# USB_hub.net
KiCad netlist of a schematic drawn in EasyEDA Pro
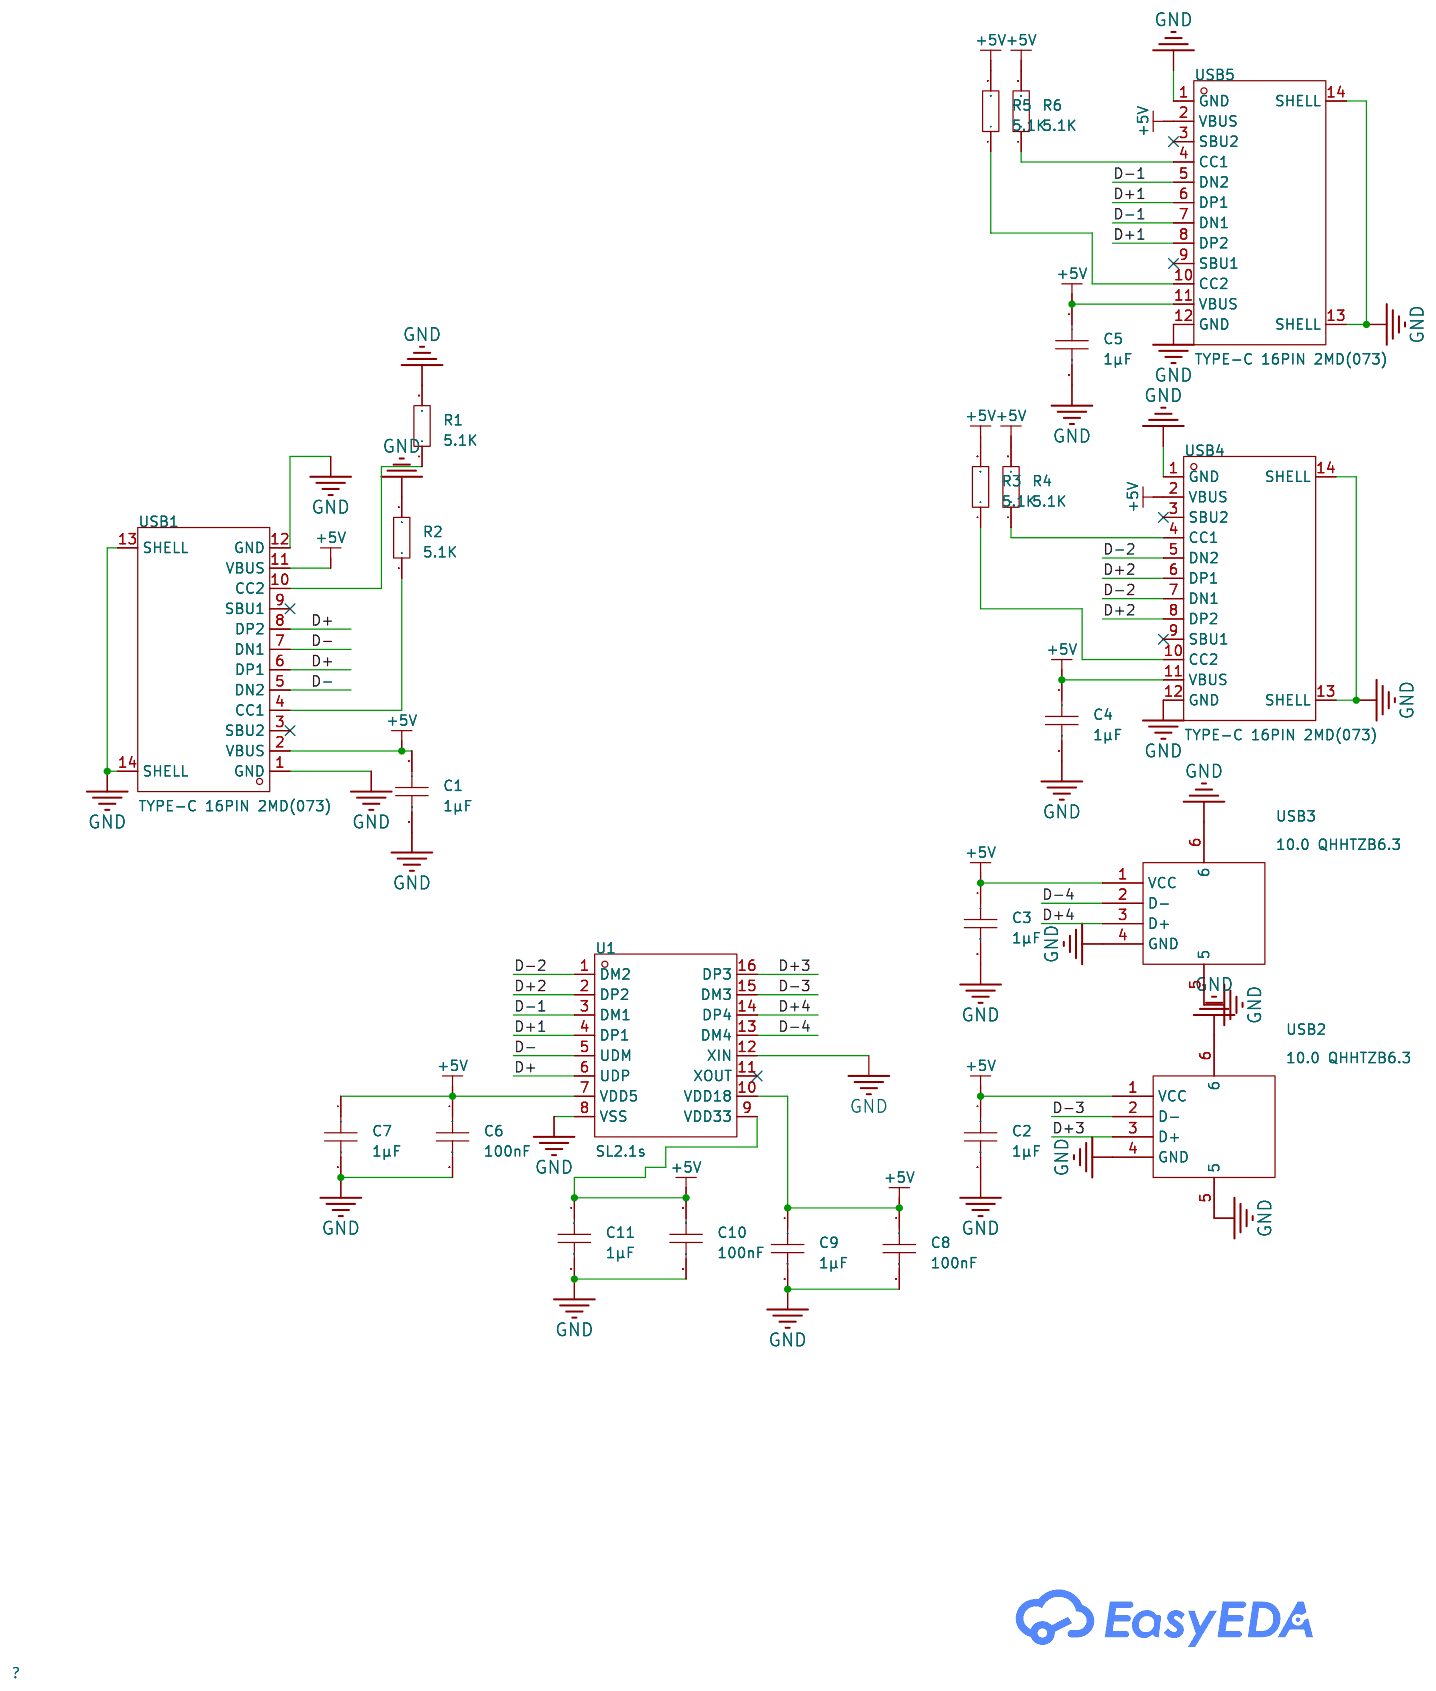
[diagram p0: schematic sheet]

(export (version "E")
  (design (tool "Eeschema 10.0.6"))
  (components
    (comp (ref "C1") (value "1µF") (footprint "easyedapro:C0603") (libsource (lib "easyedapro") (part "CAP")))
    (comp (ref "C2") (value "1µF") (footprint "easyedapro:C0603") (libsource (lib "easyedapro") (part "CAP")))
    (comp (ref "C3") (value "1µF") (footprint "easyedapro:C0603") (libsource (lib "easyedapro") (part "CAP")))
    (comp (ref "C4") (value "1µF") (footprint "easyedapro:C0603") (libsource (lib "easyedapro") (part "CAP")))
    (comp (ref "C5") (value "1µF") (footprint "easyedapro:C0603") (libsource (lib "easyedapro") (part "CAP")))
    (comp (ref "C6")
      (value "100nF")
      (footprint "easyedapro:C0603")
      (libsource (lib "easyedapro") (part "CAP"))
    )
    (comp (ref "C7") (value "1µF") (footprint "easyedapro:C0603") (libsource (lib "easyedapro") (part "CAP")))
    (comp (ref "C8")
      (value "100nF")
      (footprint "easyedapro:C0603")
      (libsource (lib "easyedapro") (part "CAP"))
    )
    (comp (ref "C9") (value "1µF") (footprint "easyedapro:C0603") (libsource (lib "easyedapro") (part "CAP")))
    (comp (ref "C10")
      (value "100nF")
      (footprint "easyedapro:C0603")
      (libsource (lib "easyedapro") (part "CAP"))
    )
    (comp (ref "C11")
      (value "1µF")
      (footprint "easyedapro:C0603")
      (libsource (lib "easyedapro") (part "CAP"))
    )
    (comp (ref "R1")
      (value "5.1K")
      (footprint "easyedapro:R0603")
      (libsource (lib "easyedapro") (part "Res"))
    )
    (comp (ref "R2")
      (value "5.1K")
      (footprint "easyedapro:R0603")
      (libsource (lib "easyedapro") (part "Res"))
    )
    (comp (ref "R3")
      (value "5.1K")
      (footprint "easyedapro:R0603")
      (libsource (lib "easyedapro") (part "Res"))
    )
    (comp (ref "R4")
      (value "5.1K")
      (footprint "easyedapro:R0603")
      (libsource (lib "easyedapro") (part "Res"))
    )
    (comp (ref "R5")
      (value "5.1K")
      (footprint "easyedapro:R0603")
      (libsource (lib "easyedapro") (part "Res"))
    )
    (comp (ref "R6")
      (value "5.1K")
      (footprint "easyedapro:R0603")
      (libsource (lib "easyedapro") (part "Res"))
    )
    (comp (ref "U1")
      (value "SL2.1s")
      (footprint "easyedapro:SSOP-16_L4.6-W2.6-P0.53-LS4.0-BL")
      (fields (field (name "Manufacturer") "CoreChips(和芯润德)"))
      (libsource (lib "easyedapro") (part "SL2.1S"))
    )
    (comp (ref "USB1")
      (value "TYPE-C 16PIN 2MD(073)")
      (footprint "easyedapro:USB-C-SMD_TYPE-C-6PIN-2MD-073")
      (fields (field (name "Manufacturer") "SHOU HAN(首韩)"))
      (libsource (lib "easyedapro") (part "TYPE-C 16PIN 2MD(073)"))
    )
    (comp (ref "USB2")
      (value "10.0 QHHTZB6.3")
      (footprint "easyedapro:USB-A-TH_10.0QHHTZB6.3")
      (fields (field (name "Manufacturer") "SHOU HAN(首韩)"))
      (libsource (lib "easyedapro") (part "10.0 QHHTZB6.3"))
    )
    (comp (ref "USB3")
      (value "10.0 QHHTZB6.3")
      (footprint "easyedapro:USB-A-TH_10.0QHHTZB6.3")
      (fields (field (name "Manufacturer") "SHOU HAN(首韩)"))
      (libsource (lib "easyedapro") (part "10.0 QHHTZB6.3"))
    )
    (comp (ref "USB4")
      (value "TYPE-C 16PIN 2MD(073)")
      (footprint "easyedapro:USB-C-SMD_TYPE-C-6PIN-2MD-073")
      (fields (field (name "Manufacturer") "SHOU HAN(首韩)"))
      (libsource (lib "easyedapro") (part "TYPE-C 16PIN 2MD(073)"))
    )
    (comp (ref "USB5")
      (value "TYPE-C 16PIN 2MD(073)")
      (footprint "easyedapro:USB-C-SMD_TYPE-C-6PIN-2MD-073")
      (fields (field (name "Manufacturer") "SHOU HAN(首韩)"))
      (libsource (lib "easyedapro") (part "TYPE-C 16PIN 2MD(073)"))
    )
  )
  (nets
    (net (code "1") (name "+5V") (class "Default")
      (node (ref "C1") (pin "1") (pinfunction "1_1") (pintype "input"))
      (node (ref "C10") (pin "1") (pinfunction "1_1") (pintype "input"))
      (node (ref "C11") (pin "1") (pinfunction "1_1") (pintype "input"))
      (node (ref "C2") (pin "1") (pinfunction "1_1") (pintype "input"))
      (node (ref "C3") (pin "1") (pinfunction "1_1") (pintype "input"))
      (node (ref "C4") (pin "1") (pinfunction "1_1") (pintype "input"))
      (node (ref "C5") (pin "1") (pinfunction "1_1") (pintype "input"))
      (node (ref "C6") (pin "1") (pinfunction "1_1") (pintype "input"))
      (node (ref "C7") (pin "1") (pinfunction "1_1") (pintype "input"))
      (node (ref "C8") (pin "1") (pinfunction "1_1") (pintype "input"))
      (node (ref "C9") (pin "1") (pinfunction "1_1") (pintype "input"))
      (node (ref "R3") (pin "2") (pinfunction "2_2") (pintype "input"))
      (node (ref "R4") (pin "2") (pinfunction "2_2") (pintype "input"))
      (node (ref "R5") (pin "2") (pinfunction "2_2") (pintype "input"))
      (node (ref "R6") (pin "2") (pinfunction "2_2") (pintype "input"))
      (node (ref "U1") (pin "10") (pinfunction "VDD18_10") (pintype "unspecified"))
      (node (ref "U1") (pin "7") (pinfunction "VDD5_7") (pintype "unspecified"))
      (node (ref "U1") (pin "9") (pinfunction "VDD33_9") (pintype "unspecified"))
      (node (ref "USB1") (pin "11") (pinfunction "VBUS_11") (pintype "unspecified"))
      (node (ref "USB1") (pin "2") (pinfunction "VBUS_2") (pintype "unspecified"))
      (node (ref "USB2") (pin "1") (pinfunction "VCC_1") (pintype "unspecified"))
      (node (ref "USB3") (pin "1") (pinfunction "VCC_1") (pintype "unspecified"))
      (node (ref "USB4") (pin "11") (pinfunction "VBUS_11") (pintype "unspecified"))
      (node (ref "USB4") (pin "2") (pinfunction "VBUS_2") (pintype "unspecified"))
      (node (ref "USB5") (pin "11") (pinfunction "VBUS_11") (pintype "unspecified"))
      (node (ref "USB5") (pin "2") (pinfunction "VBUS_2") (pintype "unspecified"))
    )
    (net (code "2") (name "/D+") (class "Default")
      (node (ref "U1") (pin "6") (pinfunction "UDP_6") (pintype "unspecified"))
      (node (ref "USB1") (pin "6") (pinfunction "DP1_6") (pintype "unspecified"))
      (node (ref "USB1") (pin "8") (pinfunction "DP2_8") (pintype "unspecified"))
    )
    (net (code "3") (name "/D+1") (class "Default")
      (node (ref "U1") (pin "4") (pinfunction "DP1_4") (pintype "unspecified"))
      (node (ref "USB5") (pin "6") (pinfunction "DP1_6") (pintype "unspecified"))
      (node (ref "USB5") (pin "8") (pinfunction "DP2_8") (pintype "unspecified"))
    )
    (net (code "4") (name "/D+2") (class "Default")
      (node (ref "U1") (pin "2") (pinfunction "DP2_2") (pintype "unspecified"))
      (node (ref "USB4") (pin "6") (pinfunction "DP1_6") (pintype "unspecified"))
      (node (ref "USB4") (pin "8") (pinfunction "DP2_8") (pintype "unspecified"))
    )
    (net (code "5") (name "/D+3") (class "Default")
      (node (ref "U1") (pin "16") (pinfunction "DP3_16") (pintype "unspecified"))
      (node (ref "USB2") (pin "3") (pinfunction "D+_3") (pintype "unspecified"))
    )
    (net (code "6") (name "/D+4") (class "Default")
      (node (ref "U1") (pin "14") (pinfunction "DP4_14") (pintype "unspecified"))
      (node (ref "USB3") (pin "3") (pinfunction "D+_3") (pintype "unspecified"))
    )
    (net (code "7") (name "/D-") (class "Default")
      (node (ref "U1") (pin "5") (pinfunction "UDM_5") (pintype "unspecified"))
      (node (ref "USB1") (pin "5") (pinfunction "DN2_5") (pintype "unspecified"))
      (node (ref "USB1") (pin "7") (pinfunction "DN1_7") (pintype "unspecified"))
    )
    (net (code "8") (name "/D-1") (class "Default")
      (node (ref "U1") (pin "3") (pinfunction "DM1_3") (pintype "unspecified"))
      (node (ref "USB5") (pin "5") (pinfunction "DN2_5") (pintype "unspecified"))
      (node (ref "USB5") (pin "7") (pinfunction "DN1_7") (pintype "unspecified"))
    )
    (net (code "9") (name "/D-2") (class "Default")
      (node (ref "U1") (pin "1") (pinfunction "DM2_1") (pintype "unspecified"))
      (node (ref "USB4") (pin "5") (pinfunction "DN2_5") (pintype "unspecified"))
      (node (ref "USB4") (pin "7") (pinfunction "DN1_7") (pintype "unspecified"))
    )
    (net (code "10") (name "/D-3") (class "Default")
      (node (ref "U1") (pin "15") (pinfunction "DM3_15") (pintype "unspecified"))
      (node (ref "USB2") (pin "2") (pinfunction "D-_2") (pintype "unspecified"))
    )
    (net (code "11") (name "/D-4") (class "Default")
      (node (ref "U1") (pin "13") (pinfunction "DM4_13") (pintype "unspecified"))
      (node (ref "USB3") (pin "2") (pinfunction "D-_2") (pintype "unspecified"))
    )
    (net (code "12") (name "GND") (class "Default")
      (node (ref "C1") (pin "2") (pinfunction "2_2") (pintype "input"))
      (node (ref "C10") (pin "2") (pinfunction "2_2") (pintype "input"))
      (node (ref "C11") (pin "2") (pinfunction "2_2") (pintype "input"))
      (node (ref "C2") (pin "2") (pinfunction "2_2") (pintype "input"))
      (node (ref "C3") (pin "2") (pinfunction "2_2") (pintype "input"))
      (node (ref "C4") (pin "2") (pinfunction "2_2") (pintype "input"))
      (node (ref "C5") (pin "2") (pinfunction "2_2") (pintype "input"))
      (node (ref "C6") (pin "2") (pinfunction "2_2") (pintype "input"))
      (node (ref "C7") (pin "2") (pinfunction "2_2") (pintype "input"))
      (node (ref "C8") (pin "2") (pinfunction "2_2") (pintype "input"))
      (node (ref "C9") (pin "2") (pinfunction "2_2") (pintype "input"))
      (node (ref "R1") (pin "2") (pinfunction "2_2") (pintype "input"))
      (node (ref "R2") (pin "2") (pinfunction "2_2") (pintype "input"))
      (node (ref "U1") (pin "12") (pinfunction "XIN_12") (pintype "unspecified"))
      (node (ref "U1") (pin "8") (pinfunction "VSS_8") (pintype "unspecified"))
      (node (ref "USB1") (pin "1") (pinfunction "GND_1") (pintype "unspecified"))
      (node (ref "USB1") (pin "12") (pinfunction "GND_12") (pintype "unspecified"))
      (node (ref "USB1") (pin "13") (pinfunction "SHELL_13") (pintype "unspecified"))
      (node (ref "USB1") (pin "14") (pinfunction "SHELL_14") (pintype "unspecified"))
      (node (ref "USB2") (pin "4") (pinfunction "GND_4") (pintype "unspecified"))
      (node (ref "USB2") (pin "5") (pinfunction "5_5") (pintype "unspecified"))
      (node (ref "USB2") (pin "6") (pinfunction "6_6") (pintype "unspecified"))
      (node (ref "USB3") (pin "4") (pinfunction "GND_4") (pintype "unspecified"))
      (node (ref "USB3") (pin "5") (pinfunction "5_5") (pintype "unspecified"))
      (node (ref "USB3") (pin "6") (pinfunction "6_6") (pintype "unspecified"))
      (node (ref "USB4") (pin "1") (pinfunction "GND_1") (pintype "unspecified"))
      (node (ref "USB4") (pin "12") (pinfunction "GND_12") (pintype "unspecified"))
      (node (ref "USB4") (pin "13") (pinfunction "SHELL_13") (pintype "unspecified"))
      (node (ref "USB4") (pin "14") (pinfunction "SHELL_14") (pintype "unspecified"))
      (node (ref "USB5") (pin "1") (pinfunction "GND_1") (pintype "unspecified"))
      (node (ref "USB5") (pin "12") (pinfunction "GND_12") (pintype "unspecified"))
      (node (ref "USB5") (pin "13") (pinfunction "SHELL_13") (pintype "unspecified"))
      (node (ref "USB5") (pin "14") (pinfunction "SHELL_14") (pintype "unspecified"))
    )
    (net (code "13") (name "Net-(USB1-CC1)") (class "Default")
      (node (ref "R2") (pin "1") (pinfunction "1_1") (pintype "input"))
      (node (ref "USB1") (pin "4") (pinfunction "CC1_4") (pintype "unspecified"))
    )
    (net (code "14") (name "Net-(USB1-CC2)") (class "Default")
      (node (ref "R1") (pin "1") (pinfunction "1_1") (pintype "input"))
      (node (ref "USB1") (pin "10") (pinfunction "CC2_10") (pintype "unspecified"))
    )
    (net (code "15") (name "Net-(USB4-CC1)") (class "Default")
      (node (ref "R4") (pin "1") (pinfunction "1_1") (pintype "input"))
      (node (ref "USB4") (pin "4") (pinfunction "CC1_4") (pintype "unspecified"))
    )
    (net (code "16") (name "Net-(USB4-CC2)") (class "Default")
      (node (ref "R3") (pin "1") (pinfunction "1_1") (pintype "input"))
      (node (ref "USB4") (pin "10") (pinfunction "CC2_10") (pintype "unspecified"))
    )
    (net (code "17") (name "Net-(USB5-CC1)") (class "Default")
      (node (ref "R6") (pin "1") (pinfunction "1_1") (pintype "input"))
      (node (ref "USB5") (pin "4") (pinfunction "CC1_4") (pintype "unspecified"))
    )
    (net (code "18") (name "Net-(USB5-CC2)") (class "Default")
      (node (ref "R5") (pin "1") (pinfunction "1_1") (pintype "input"))
      (node (ref "USB5") (pin "10") (pinfunction "CC2_10") (pintype "unspecified"))
    )
    (net (code "19") (name "unconnected-(U1-XOUT-Pad11)") (class "Default")
      (node (ref "U1") (pin "11") (pinfunction "XOUT_11") (pintype "unspecified+no_connect"))
    )
    (net (code "20") (name "unconnected-(USB1-SBU1-Pad9)") (class "Default")
      (node (ref "USB1") (pin "9") (pinfunction "SBU1_9") (pintype "unspecified+no_connect"))
    )
    (net (code "21") (name "unconnected-(USB1-SBU2-Pad3)") (class "Default")
      (node (ref "USB1") (pin "3") (pinfunction "SBU2_3") (pintype "unspecified+no_connect"))
    )
    (net (code "22") (name "unconnected-(USB4-SBU1-Pad9)") (class "Default")
      (node (ref "USB4") (pin "9") (pinfunction "SBU1_9") (pintype "unspecified+no_connect"))
    )
    (net (code "23") (name "unconnected-(USB4-SBU2-Pad3)") (class "Default")
      (node (ref "USB4") (pin "3") (pinfunction "SBU2_3") (pintype "unspecified+no_connect"))
    )
    (net (code "24") (name "unconnected-(USB5-SBU1-Pad9)") (class "Default")
      (node (ref "USB5") (pin "9") (pinfunction "SBU1_9") (pintype "unspecified+no_connect"))
    )
    (net (code "25") (name "unconnected-(USB5-SBU2-Pad3)") (class "Default")
      (node (ref "USB5") (pin "3") (pinfunction "SBU2_3") (pintype "unspecified+no_connect"))
    )
  )
)
